# 2_-_Control.net
KiCad netlist of a schematic drawn in Altium Designer
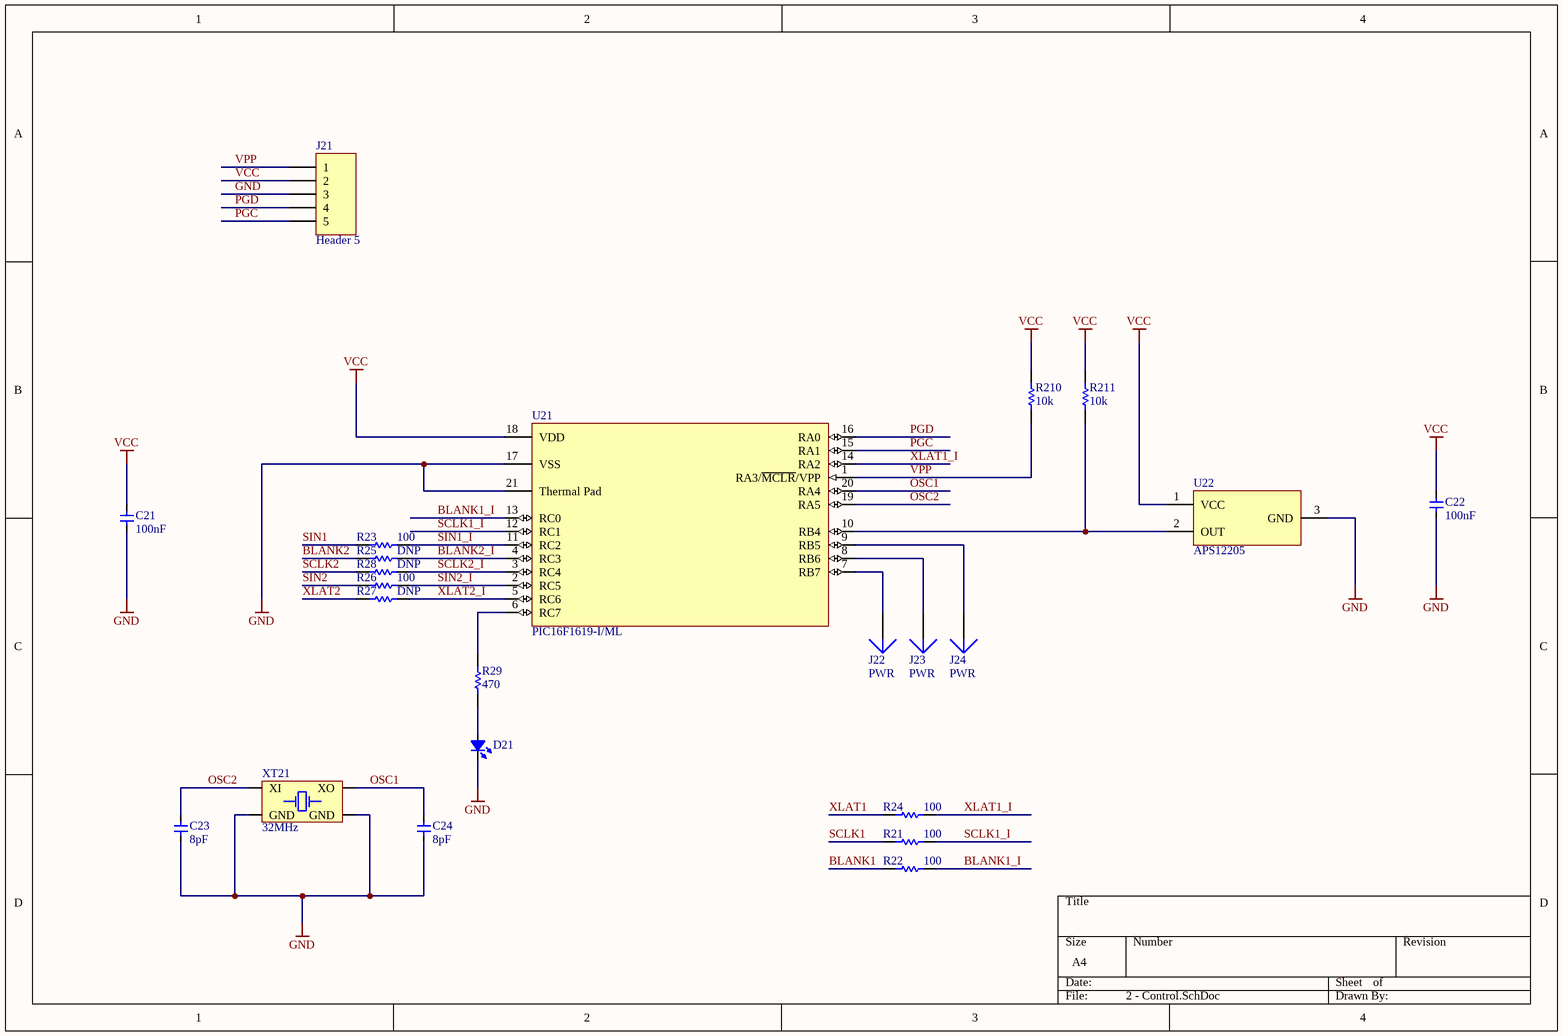
[diagram p0: 2 - Control.SchDoc]

(export (version "E")
  (design (tool "Eeschema 10.0.6"))
  (components
    (comp (ref "C21")
      (value "100nF")
      (footprint "PCB_PassiveCap:CAP_0603")
      (description "Capacitor")
      (fields (field (name "Comment") "Cap_0603"))
      (libsource (lib "SCH_Passive") (part "Cap_0603"))
    )
    (comp (ref "C22")
      (value "100nF")
      (footprint "PCB_PassiveCap:CAP_0603")
      (description "Capacitor")
      (fields (field (name "Comment") "Cap_0603"))
      (libsource (lib "SCH_Passive") (part "Cap_0603"))
    )
    (comp (ref "C23")
      (value "8pF")
      (footprint "PCB_PassiveCap:CAP_0603")
      (description "Capacitor")
      (fields (field (name "Comment") "Cap_0603"))
      (libsource (lib "SCH_Passive") (part "Cap_0603"))
    )
    (comp (ref "C24")
      (value "8pF")
      (footprint "PCB_PassiveCap:CAP_0603")
      (description "Capacitor")
      (fields (field (name "Comment") "Cap_0603"))
      (libsource (lib "SCH_Passive") (part "Cap_0603"))
    )
    (comp (ref "D21")
      (value "LED_0603")
      (footprint "PCB_ActiveLED:LED_0603_RED")
      (description "LED")
      (libsource (lib "SCH_Active") (part "LED_0603"))
    )
    (comp (ref "J21")
      (value "Header 5")
      (footprint "HDR1X5")
      (description "Header, 5-Pin")
      (fields (field (name "PUBLISHER") "Altium Limited"))
      (libsource (lib "Miscellaneous Connectors") (part "Header 5"))
    )
    (comp (ref "J22")
      (value "PWR")
      (footprint "PIN1")
      (description "Plug")
      (fields (field (name "PUBLISHER") "Altium Limited"))
      (libsource (lib "Miscellaneous Connectors") (part "Plug"))
    )
    (comp (ref "J23")
      (value "PWR")
      (footprint "PIN1")
      (description "Plug")
      (fields (field (name "PUBLISHER") "Altium Limited"))
      (libsource (lib "Miscellaneous Connectors") (part "Plug"))
    )
    (comp (ref "J24")
      (value "PWR")
      (footprint "PIN1")
      (description "Plug")
      (fields (field (name "PUBLISHER") "Altium Limited"))
      (libsource (lib "Miscellaneous Connectors") (part "Plug"))
    )
    (comp (ref "R21")
      (value "100")
      (footprint "RES_0603")
      (description "Resistor")
      (fields (field (name "Comment") "Res1") (field (name "PUBLISHER") "Altium Limited"))
      (libsource (lib "Miscellaneous Devices") (part "Res1"))
    )
    (comp (ref "R22")
      (value "100")
      (footprint "RES_0603")
      (description "Resistor")
      (fields (field (name "Comment") "Res1") (field (name "PUBLISHER") "Altium Limited"))
      (libsource (lib "Miscellaneous Devices") (part "Res1"))
    )
    (comp (ref "R23")
      (value "100")
      (footprint "RES_0603")
      (description "Resistor")
      (fields (field (name "Comment") "Res1") (field (name "PUBLISHER") "Altium Limited"))
      (libsource (lib "Miscellaneous Devices") (part "Res1"))
    )
    (comp (ref "R24")
      (value "100")
      (footprint "RES_0603")
      (description "Resistor")
      (fields (field (name "Comment") "Res1") (field (name "PUBLISHER") "Altium Limited"))
      (libsource (lib "Miscellaneous Devices") (part "Res1"))
    )
    (comp (ref "R25")
      (value "DNP")
      (footprint "RES_0603")
      (description "Resistor")
      (fields (field (name "Comment") "Res1") (field (name "PUBLISHER") "Altium Limited"))
      (libsource (lib "Miscellaneous Devices") (part "Res1"))
    )
    (comp (ref "R26")
      (value "100")
      (footprint "RES_0603")
      (description "Resistor")
      (fields (field (name "Comment") "Res1") (field (name "PUBLISHER") "Altium Limited"))
      (libsource (lib "Miscellaneous Devices") (part "Res1"))
    )
    (comp (ref "R27")
      (value "DNP")
      (footprint "RES_0603")
      (description "Resistor")
      (fields (field (name "Comment") "Res1") (field (name "PUBLISHER") "Altium Limited"))
      (libsource (lib "Miscellaneous Devices") (part "Res1"))
    )
    (comp (ref "R28")
      (value "DNP")
      (footprint "RES_0603")
      (description "Resistor")
      (fields (field (name "Comment") "Res1") (field (name "PUBLISHER") "Altium Limited"))
      (libsource (lib "Miscellaneous Devices") (part "Res1"))
    )
    (comp (ref "R29")
      (value "470")
      (footprint "RES_0603")
      (description "Resistor")
      (fields (field (name "Comment") "Res1") (field (name "PUBLISHER") "Altium Limited"))
      (libsource (lib "Miscellaneous Devices") (part "Res1"))
    )
    (comp (ref "R210")
      (value "10k")
      (footprint "RES_0603")
      (description "Resistor")
      (fields (field (name "Comment") "Res1") (field (name "PUBLISHER") "Altium Limited"))
      (libsource (lib "Miscellaneous Devices") (part "Res1"))
    )
    (comp (ref "R211")
      (value "10k")
      (footprint "RES_0603")
      (description "Resistor")
      (fields (field (name "Comment") "Res1") (field (name "PUBLISHER") "Altium Limited"))
      (libsource (lib "Miscellaneous Devices") (part "Res1"))
    )
    (comp (ref "U21")
      (value "PIC16F1619-I/ML")
      (footprint "QFN-ML20_M")
      (description "PIC PIC® XLP™ 16F Microcontroller IC 8-Bit 32MHz 14KB (8K x 14) FLASH 20-QFN (4x4)")
      (fields (field (name "PUBLISHER") "Altium Limited"))
      (libsource (lib "Jarrett") (part "PIC16F1619-I/ML"))
    )
    (comp (ref "U22")
      (value "APS12205")
      (footprint "PCB_IntegratedCircuit:SOT23-3")
      (description "Sensor Hall")
      (libsource (lib "SCH_IntegratedCircuit") (part "A32xx"))
    )
    (comp (ref "XT21")
      (value "32MHz")
      (footprint "PCB_Oscillator:XT_2520_4")
      (description "Crystal Oscillator")
      (fields (field (name "Comment") "XTAL_2520_4P"))
      (libsource (lib "SCH_Oscillator") (part "XTAL_2520_4P"))
    )
  )
  (nets
    (net (code "1") (name "/BLANK1") (class "Default")
      (node (ref "R22") (pin "2") (pinfunction "2_2") (pintype "passive"))
    )
    (net (code "2") (name "/BLANK1_I") (class "Default")
      (node (ref "R22") (pin "1") (pinfunction "1_1") (pintype "passive"))
      (node (ref "U21") (pin "13") (pinfunction "RC0_13") (pintype "bidirectional"))
    )
    (net (code "3") (name "/BLANK2") (class "Default")
      (node (ref "R25") (pin "2") (pinfunction "2_2") (pintype "passive"))
    )
    (net (code "4") (name "/BLANK2_I") (class "Default")
      (node (ref "R25") (pin "1") (pinfunction "1_1") (pintype "passive"))
      (node (ref "U21") (pin "4") (pinfunction "RC3_4") (pintype "bidirectional"))
    )
    (net (code "5") (name "/OSC1") (class "Default")
      (node (ref "C24") (pin "2") (pinfunction "2_2") (pintype "passive"))
      (node (ref "U21") (pin "20") (pinfunction "RA4_20") (pintype "bidirectional"))
      (node (ref "XT21") (pin "3") (pinfunction "XO_3") (pintype "passive"))
    )
    (net (code "6") (name "/OSC2") (class "Default")
      (node (ref "C23") (pin "2") (pinfunction "2_2") (pintype "passive"))
      (node (ref "U21") (pin "19") (pinfunction "RA5_19") (pintype "bidirectional"))
      (node (ref "XT21") (pin "1") (pinfunction "XI_1") (pintype "passive"))
    )
    (net (code "7") (name "/PGC") (class "Default")
      (node (ref "J21") (pin "5") (pinfunction "5_5") (pintype "passive"))
      (node (ref "U21") (pin "15") (pinfunction "RA1_15") (pintype "bidirectional"))
    )
    (net (code "8") (name "/PGD") (class "Default")
      (node (ref "J21") (pin "4") (pinfunction "4_4") (pintype "passive"))
      (node (ref "U21") (pin "16") (pinfunction "RA0_16") (pintype "bidirectional"))
    )
    (net (code "9") (name "/SCLK1") (class "Default")
      (node (ref "R21") (pin "2") (pinfunction "2_2") (pintype "passive"))
    )
    (net (code "10") (name "/SCLK1_I") (class "Default")
      (node (ref "R21") (pin "1") (pinfunction "1_1") (pintype "passive"))
      (node (ref "U21") (pin "12") (pinfunction "RC1_12") (pintype "bidirectional"))
    )
    (net (code "11") (name "/SCLK2") (class "Default")
      (node (ref "R28") (pin "2") (pinfunction "2_2") (pintype "passive"))
    )
    (net (code "12") (name "/SCLK2_I") (class "Default")
      (node (ref "R28") (pin "1") (pinfunction "1_1") (pintype "passive"))
      (node (ref "U21") (pin "3") (pinfunction "RC4_3") (pintype "bidirectional"))
    )
    (net (code "13") (name "/SIN1") (class "Default")
      (node (ref "R23") (pin "2") (pinfunction "2_2") (pintype "passive"))
    )
    (net (code "14") (name "/SIN1_I") (class "Default")
      (node (ref "R23") (pin "1") (pinfunction "1_1") (pintype "passive"))
      (node (ref "U21") (pin "11") (pinfunction "RC2_11") (pintype "bidirectional"))
    )
    (net (code "15") (name "/SIN2") (class "Default")
      (node (ref "R26") (pin "2") (pinfunction "2_2") (pintype "passive"))
    )
    (net (code "16") (name "/SIN2_I") (class "Default")
      (node (ref "R26") (pin "1") (pinfunction "1_1") (pintype "passive"))
      (node (ref "U21") (pin "2") (pinfunction "RC5_2") (pintype "bidirectional"))
    )
    (net (code "17") (name "/VPP") (class "Default")
      (node (ref "J21") (pin "1") (pinfunction "1_1") (pintype "passive"))
      (node (ref "R210") (pin "1") (pinfunction "1_1") (pintype "passive"))
      (node (ref "U21") (pin "1") (pinfunction "RA3/~{MCLR}/VPP_1") (pintype "input"))
    )
    (net (code "18") (name "/XLAT1") (class "Default")
      (node (ref "R24") (pin "2") (pinfunction "2_2") (pintype "passive"))
    )
    (net (code "19") (name "/XLAT1_I") (class "Default")
      (node (ref "R24") (pin "1") (pinfunction "1_1") (pintype "passive"))
      (node (ref "U21") (pin "14") (pinfunction "RA2_14") (pintype "bidirectional"))
    )
    (net (code "20") (name "/XLAT2") (class "Default")
      (node (ref "R27") (pin "2") (pinfunction "2_2") (pintype "passive"))
    )
    (net (code "21") (name "/XLAT2_I") (class "Default")
      (node (ref "R27") (pin "1") (pinfunction "1_1") (pintype "passive"))
      (node (ref "U21") (pin "5") (pinfunction "RC6_5") (pintype "bidirectional"))
    )
    (net (code "22") (name "GND") (class "Default")
      (node (ref "C21") (pin "1") (pinfunction "1_1") (pintype "passive"))
      (node (ref "C22") (pin "1") (pinfunction "1_1") (pintype "passive"))
      (node (ref "C23") (pin "1") (pinfunction "1_1") (pintype "passive"))
      (node (ref "C24") (pin "1") (pinfunction "1_1") (pintype "passive"))
      (node (ref "D21") (pin "2") (pinfunction "K_2") (pintype "passive"))
      (node (ref "J21") (pin "3") (pinfunction "3_3") (pintype "passive"))
      (node (ref "U21") (pin "17") (pinfunction "VSS_17") (pintype "power_in"))
      (node (ref "U21") (pin "21") (pinfunction "Thermal_Pad_21") (pintype "power_in"))
      (node (ref "U22") (pin "3") (pinfunction "GND_3") (pintype "passive"))
      (node (ref "XT21") (pin "2") (pinfunction "GND_2") (pintype "passive"))
      (node (ref "XT21") (pin "4") (pinfunction "GND_4") (pintype "passive"))
    )
    (net (code "23") (name "Net-(D21-A)") (class "Default")
      (node (ref "D21") (pin "1") (pinfunction "A_1") (pintype "passive"))
      (node (ref "R29") (pin "1") (pinfunction "1_1") (pintype "passive"))
    )
    (net (code "24") (name "Net-(U21-RB4)") (class "Default")
      (node (ref "R211") (pin "1") (pinfunction "1_1") (pintype "passive"))
      (node (ref "U21") (pin "10") (pinfunction "RB4_10") (pintype "bidirectional"))
      (node (ref "U22") (pin "2") (pinfunction "OUT_2") (pintype "passive"))
    )
    (net (code "25") (name "Net-(U21-RB5)") (class "Default")
      (node (ref "J24") (pin "1") (pinfunction "1_1") (pintype "passive"))
      (node (ref "U21") (pin "9") (pinfunction "RB5_9") (pintype "bidirectional"))
    )
    (net (code "26") (name "Net-(U21-RB6)") (class "Default")
      (node (ref "J23") (pin "1") (pinfunction "1_1") (pintype "passive"))
      (node (ref "U21") (pin "8") (pinfunction "RB6_8") (pintype "bidirectional"))
    )
    (net (code "27") (name "Net-(U21-RB7)") (class "Default")
      (node (ref "J22") (pin "1") (pinfunction "1_1") (pintype "passive"))
      (node (ref "U21") (pin "7") (pinfunction "RB7_7") (pintype "bidirectional"))
    )
    (net (code "28") (name "Net-(U21-RC7)") (class "Default")
      (node (ref "R29") (pin "2") (pinfunction "2_2") (pintype "passive"))
      (node (ref "U21") (pin "6") (pinfunction "RC7_6") (pintype "bidirectional"))
    )
    (net (code "29") (name "VCC") (class "Default")
      (node (ref "C21") (pin "2") (pinfunction "2_2") (pintype "passive"))
      (node (ref "C22") (pin "2") (pinfunction "2_2") (pintype "passive"))
      (node (ref "J21") (pin "2") (pinfunction "2_2") (pintype "passive"))
      (node (ref "R210") (pin "2") (pinfunction "2_2") (pintype "passive"))
      (node (ref "R211") (pin "2") (pinfunction "2_2") (pintype "passive"))
      (node (ref "U21") (pin "18") (pinfunction "VDD_18") (pintype "power_in"))
      (node (ref "U22") (pin "1") (pinfunction "VCC_1") (pintype "passive"))
    )
  )
)
